# Omniband_v1-05-22_EVT_TPS_30101DRI_PL_FI.net
KiCad netlist of a schematic drawn in EAGLE
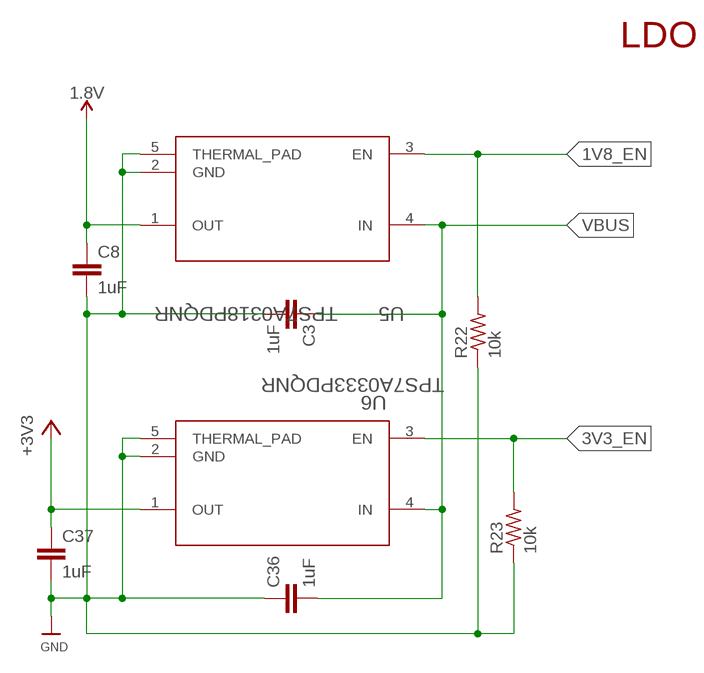
[diagram p0: schematic, sheet 1]

(export (version "E")
  (design (tool "Eeschema 10.0.6"))
  (components
    (comp (ref "C3")
      (value "1uF")
      (footprint "eagle-import:C0201")
      (libsource (lib "eagle-import") (part "C-EUC0201"))
    )
    (comp (ref "C8")
      (value "1uF")
      (footprint "eagle-import:C0201")
      (libsource (lib "eagle-import") (part "C-EUC0201"))
    )
    (comp (ref "C36")
      (value "1uF")
      (footprint "eagle-import:C0201")
      (libsource (lib "eagle-import") (part "C-EUC0201"))
    )
    (comp (ref "C37")
      (value "1uF")
      (footprint "eagle-import:C0201")
      (libsource (lib "eagle-import") (part "C-EUC0201"))
    )
    (comp (ref "R22")
      (value "10k")
      (footprint "eagle-import:R0201")
      (libsource (lib "eagle-import") (part "R-US_R0201"))
    )
    (comp (ref "R23")
      (value "10k")
      (footprint "eagle-import:R0201")
      (libsource (lib "eagle-import") (part "R-US_R0201"))
    )
    (comp (ref "U5")
      (value "TPS7A0318PDQNR")
      (footprint "eagle-import:DQN0004A-MFG")
      (fields (field (name "COPYRIGHT") "Copyright (C) 2025 Ultra Librarian. All rights reserved."))
      (libsource (lib "eagle-import") (part "TPS7A0318PDQNR"))
    )
    (comp (ref "U6")
      (value "TPS7A0333PDQNR")
      (footprint "eagle-import:DQN0004A-MFG")
      (fields (field (name "COPYRIGHT") "Copyright (C) 2025 Ultra Librarian. All rights reserved."))
      (libsource (lib "eagle-import") (part "TPS7A0333PDQNR"))
    )
  )
  (nets
    (net (code "1") (name "+3V3") (class "Default")
      (node (ref "C37") (pin "1") (pinfunction "1_1") (pintype "passive"))
      (node (ref "U6") (pin "1") (pinfunction "OUT_1") (pintype "power_in"))
    )
    (net (code "2") (name "1.8V") (class "Default")
      (node (ref "C8") (pin "1") (pinfunction "1_1") (pintype "passive"))
      (node (ref "U5") (pin "1") (pinfunction "OUT_1") (pintype "power_in"))
    )
    (net (code "3") (name "1V8_EN") (class "Default")
      (node (ref "R22") (pin "2") (pinfunction "2_2") (pintype "passive"))
      (node (ref "U5") (pin "3") (pinfunction "EN_3") (pintype "input"))
    )
    (net (code "4") (name "3V3_EN") (class "Default")
      (node (ref "R23") (pin "2") (pinfunction "2_2") (pintype "passive"))
      (node (ref "U6") (pin "3") (pinfunction "EN_3") (pintype "input"))
    )
    (net (code "5") (name "GND") (class "Default")
      (node (ref "C3") (pin "2") (pinfunction "2_2") (pintype "passive"))
      (node (ref "C36") (pin "1") (pinfunction "1_1") (pintype "passive"))
      (node (ref "C37") (pin "2") (pinfunction "2_2") (pintype "passive"))
      (node (ref "C8") (pin "2") (pinfunction "2_2") (pintype "passive"))
      (node (ref "R22") (pin "1") (pinfunction "1_1") (pintype "passive"))
      (node (ref "R23") (pin "1") (pinfunction "1_1") (pintype "passive"))
      (node (ref "U5") (pin "2") (pinfunction "GND_2") (pintype "power_in"))
      (node (ref "U5") (pin "5") (pinfunction "THERMAL_PAD_5") (pintype "passive"))
      (node (ref "U6") (pin "2") (pinfunction "GND_2") (pintype "power_in"))
      (node (ref "U6") (pin "5") (pinfunction "THERMAL_PAD_5") (pintype "passive"))
    )
    (net (code "6") (name "VBUS") (class "Default")
      (node (ref "C3") (pin "1") (pinfunction "1_1") (pintype "passive"))
      (node (ref "C36") (pin "2") (pinfunction "2_2") (pintype "passive"))
      (node (ref "U5") (pin "4") (pinfunction "IN_4") (pintype "power_in"))
      (node (ref "U6") (pin "4") (pinfunction "IN_4") (pintype "power_in"))
    )
  )
)
